# LTM8051.net
KiCad netlist of a schematic drawn in Altium Designer
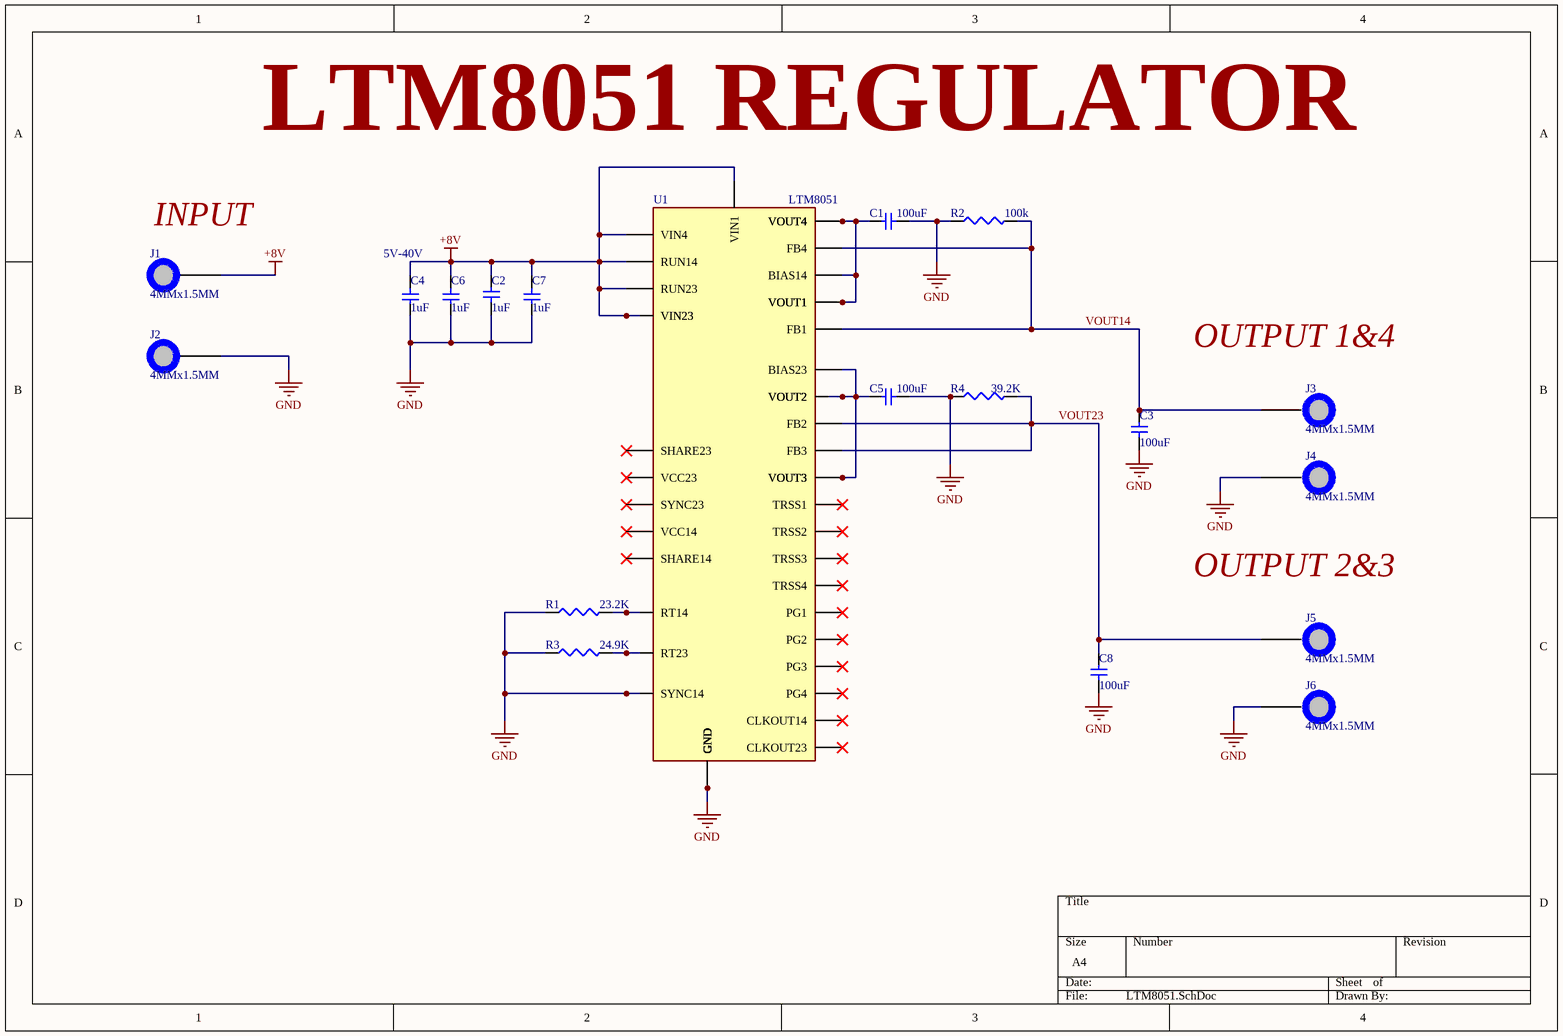
[diagram p0: LTM8051.SchDoc]

(export (version "E")
  (design (tool "Eeschema 10.0.6"))
  (components
    (comp (ref "C1")
      (value "100uF")
      (footprint "C0805")
      (description "100UF 6.3V 20% 0805")
      (fields
        (field (name "MANUFACTURER") "Kyocera AVX")
        (field (name "MANUFACTURER PART NUMBER") "CM21X5R107M06AT")
      )
      (libsource (lib "LTM8051") (part "CM21X5R107M06AT"))
    )
    (comp (ref "C2")
      (value "1uF")
      (footprint "C0805")
      (description "Cap Ceramic 1uF 50V X5R 20% SMD 0805 85°C Punched Paper T/R")
      (fields
        (field (name "MANUFACTURER") "TDK")
        (field (name "MANUFACTURER PART NUMBER") "C2012X5R1H105M085AB")
      )
      (libsource (lib "LTM8051") (part "C2012X5R1H105M085AB"))
    )
    (comp (ref "C3")
      (value "100uF")
      (footprint "C0805")
      (description "100UF 6.3V 20% 0805")
      (fields
        (field (name "MANUFACTURER") "Kyocera AVX")
        (field (name "MANUFACTURER PART NUMBER") "CM21X5R107M06AT")
      )
      (libsource (lib "LTM8051") (part "CM21X5R107M06AT"))
    )
    (comp (ref "C4")
      (value "1uF")
      (footprint "C0805")
      (description "Cap Ceramic 1uF 50V X5R 20% SMD 0805 85°C Punched Paper T/R")
      (fields
        (field (name "MANUFACTURER") "TDK")
        (field (name "MANUFACTURER PART NUMBER") "C2012X5R1H105M085AB")
      )
      (libsource (lib "LTM8051") (part "C2012X5R1H105M085AB"))
    )
    (comp (ref "C5")
      (value "100uF")
      (footprint "C0805")
      (description "100UF 6.3V 20% 0805")
      (fields
        (field (name "MANUFACTURER") "Kyocera AVX")
        (field (name "MANUFACTURER PART NUMBER") "CM21X5R107M06AT")
      )
      (libsource (lib "LTM8051") (part "CM21X5R107M06AT"))
    )
    (comp (ref "C6")
      (value "1uF")
      (footprint "C0805")
      (description "Cap Ceramic 1uF 50V X5R 20% SMD 0805 85°C Punched Paper T/R")
      (fields
        (field (name "MANUFACTURER") "TDK")
        (field (name "MANUFACTURER PART NUMBER") "C2012X5R1H105M085AB")
      )
      (libsource (lib "LTM8051") (part "C2012X5R1H105M085AB"))
    )
    (comp (ref "C7")
      (value "1uF")
      (footprint "C0805")
      (description "Cap Ceramic 1uF 50V X5R 20% SMD 0805 85°C Punched Paper T/R")
      (fields
        (field (name "MANUFACTURER") "TDK")
        (field (name "MANUFACTURER PART NUMBER") "C2012X5R1H105M085AB")
      )
      (libsource (lib "LTM8051") (part "C2012X5R1H105M085AB"))
    )
    (comp (ref "C8")
      (value "100uF")
      (footprint "C0805")
      (description "100UF 6.3V 20% 0805")
      (fields
        (field (name "MANUFACTURER") "Kyocera AVX")
        (field (name "MANUFACTURER PART NUMBER") "CM21X5R107M06AT")
      )
      (libsource (lib "LTM8051") (part "CM21X5R107M06AT"))
    )
    (comp (ref "J1")
      (value "4MMx1.5MM")
      (footprint "PAD_WITH_HOLE_4MMx1MM5")
      (description "Pad with a hole 4mmx1.5mm")
      (libsource (lib "LTM8051") (part "PAD_WITH_HOLE_4MMx1MM5"))
    )
    (comp (ref "J2")
      (value "4MMx1.5MM")
      (footprint "PAD_WITH_HOLE_4MMx1MM5")
      (description "Pad with a hole 4mmx1.5mm")
      (libsource (lib "LTM8051") (part "PAD_WITH_HOLE_4MMx1MM5"))
    )
    (comp (ref "J3")
      (value "4MMx1.5MM")
      (footprint "PAD_WITH_HOLE_4MMx1MM5")
      (description "Pad with a hole 4mmx1.5mm")
      (libsource (lib "LTM8051") (part "PAD_WITH_HOLE_4MMx1MM5"))
    )
    (comp (ref "J4")
      (value "4MMx1.5MM")
      (footprint "PAD_WITH_HOLE_4MMx1MM5")
      (description "Pad with a hole 4mmx1.5mm")
      (libsource (lib "LTM8051") (part "PAD_WITH_HOLE_4MMx1MM5"))
    )
    (comp (ref "J5")
      (value "4MMx1.5MM")
      (footprint "PAD_WITH_HOLE_4MMx1MM5")
      (description "Pad with a hole 4mmx1.5mm")
      (libsource (lib "LTM8051") (part "PAD_WITH_HOLE_4MMx1MM5"))
    )
    (comp (ref "J6")
      (value "4MMx1.5MM")
      (footprint "PAD_WITH_HOLE_4MMx1MM5")
      (description "Pad with a hole 4mmx1.5mm")
      (libsource (lib "LTM8051") (part "PAD_WITH_HOLE_4MMx1MM5"))
    )
    (comp (ref "R1")
      (value "23.2K")
      (footprint "R0805")
      (description "Res Thick Film 0805 23.2K Ohm 1% 1/8W ¦100ppm/¦C SMD Punched Carrier T/R")
      (fields
        (field (name "MANUFACTURER") "Panasonic")
        (field (name "MANUFACTURER PART NUMBER") "ERJ-6ENF2322V")
      )
      (libsource (lib "LTM8051") (part "ERJ-6ENF2322V"))
    )
    (comp (ref "R2")
      (value "100k")
      (footprint "R0805")
      (description "Res Thin Film 0805 100K Ohm 0.1% 1/8W ±25ppm/°C Molded SMD SMD Punched Carrier T/R")
      (fields
        (field (name "MANUFACTURER") "Panasonic")
        (field (name "MANUFACTURER PART NUMBER") "ERA-6AEB104V")
      )
      (libsource (lib "LTM8051") (part "ERA-6AEB104V"))
    )
    (comp (ref "R3")
      (value "24.9K")
      (footprint "R0805")
      (description "SMD Chip Resistor, 24.9 kOhm, ± 1%, 125 mW, 0805 [2012 Metric], Thick Film, General Purpose")
      (fields
        (field (name "MANUFACTURER") "Yageo")
        (field (name "MANUFACTURER PART NUMBER") "AC0805FR-0724K9L")
      )
      (libsource (lib "LTM8051") (part "AC0805FR-0724K9L"))
    )
    (comp (ref "R4")
      (value "39.2K")
      (footprint "R0805")
      (description "Res Thick Film 0805 39.2K Ohm 1% 1/8W ±100ppm/°C Molded SMD Punched Carrier T/R")
      (fields
        (field (name "MANUFACTURER") "Panasonic")
        (field (name "MANUFACTURER PART NUMBER") "ERJ-6ENF3922V")
      )
      (libsource (lib "LTM8051") (part "ERJ-6ENF3922V"))
    )
    (comp (ref "U1")
      (value "LTM8051")
      (footprint "BGA91C80P7X13_625X1125X241")
      (description "Switching Regulator, Current-mode, 2.5A, 3000kHz Switching Freq-Max, Hybrid, PBGA91")
      (fields
        (field (name "MANUFACTURER") "Analog Devices")
        (field (name "MANUFACTURER PART NUMBER") "LTM8051EY#PBF")
      )
      (libsource (lib "LTM8051") (part "LTM8051EY#PBF"))
    )
  )
  (nets
    (net (code "1") (name "+8V") (class "Default")
      (node (ref "C2") (pin "2") (pinfunction "2_2") (pintype "passive"))
      (node (ref "C4") (pin "1") (pinfunction "1_1") (pintype "passive"))
      (node (ref "C6") (pin "1") (pinfunction "1_1") (pintype "passive"))
      (node (ref "C7") (pin "1") (pinfunction "1_1") (pintype "passive"))
      (node (ref "J1") (pin "1") (pinfunction "1_1") (pintype "passive"))
      (node (ref "U1") (pin "C7") (pinfunction "RUN23_C7") (pintype "passive"))
      (node (ref "U1") (pin "D7") (pinfunction "RUN14_D7") (pintype "passive"))
      (node (ref "U1") (pin "E7") (pinfunction "VIN1_E7") (pintype "passive"))
      (node (ref "U1") (pin "F7") (pinfunction "VIN4_F7") (pintype "passive"))
      (node (ref "U1") (pin "G1") (pinfunction "VIN23_G1") (pintype "passive"))
      (node (ref "U1") (pin "H1") (pinfunction "VIN23_H1") (pintype "passive"))
    )
    (net (code "2") (name "/VOUT14") (class "Default")
      (node (ref "C3") (pin "2") (pinfunction "2_2") (pintype "passive"))
      (node (ref "J3") (pin "1") (pinfunction "1_1") (pintype "passive"))
      (node (ref "R2") (pin "2") (pinfunction "2_2") (pintype "passive"))
      (node (ref "U1") (pin "L1") (pinfunction "FB4_L1") (pintype "passive"))
      (node (ref "U1") (pin "L2") (pinfunction "FB1_L2") (pintype "passive"))
    )
    (net (code "3") (name "/VOUT23") (class "Default")
      (node (ref "C8") (pin "2") (pinfunction "2_2") (pintype "passive"))
      (node (ref "J5") (pin "1") (pinfunction "1_1") (pintype "passive"))
      (node (ref "R4") (pin "2") (pinfunction "2_2") (pintype "passive"))
      (node (ref "U1") (pin "D1") (pinfunction "FB3_D1") (pintype "passive"))
      (node (ref "U1") (pin "D2") (pinfunction "FB2_D2") (pintype "passive"))
    )
    (net (code "4") (name "GND") (class "Default")
      (node (ref "C1") (pin "1") (pinfunction "1_1") (pintype "passive"))
      (node (ref "C2") (pin "1") (pinfunction "1_1") (pintype "passive"))
      (node (ref "C3") (pin "1") (pinfunction "1_1") (pintype "passive"))
      (node (ref "C4") (pin "2") (pinfunction "2_2") (pintype "passive"))
      (node (ref "C5") (pin "1") (pinfunction "1_1") (pintype "passive"))
      (node (ref "C6") (pin "2") (pinfunction "2_2") (pintype "passive"))
      (node (ref "C7") (pin "2") (pinfunction "2_2") (pintype "passive"))
      (node (ref "C8") (pin "1") (pinfunction "1_1") (pintype "passive"))
      (node (ref "J2") (pin "1") (pinfunction "1_1") (pintype "passive"))
      (node (ref "J4") (pin "1") (pinfunction "1_1") (pintype "passive"))
      (node (ref "J6") (pin "1") (pinfunction "1_1") (pintype "passive"))
      (node (ref "R1") (pin "1") (pinfunction "1_1") (pintype "passive"))
      (node (ref "R2") (pin "1") (pinfunction "1_1") (pintype "passive"))
      (node (ref "R3") (pin "1") (pinfunction "1_1") (pintype "passive"))
      (node (ref "R4") (pin "1") (pinfunction "1_1") (pintype "passive"))
      (node (ref "U1") (pin "B3") (pinfunction "GND_B3") (pintype "passive"))
      (node (ref "U1") (pin "B4") (pinfunction "GND_B4") (pintype "passive"))
      (node (ref "U1") (pin "B5") (pinfunction "GND_B5") (pintype "passive"))
      (node (ref "U1") (pin "C3") (pinfunction "GND_C3") (pintype "passive"))
      (node (ref "U1") (pin "C4") (pinfunction "GND_C4") (pintype "passive"))
      (node (ref "U1") (pin "C5") (pinfunction "GND_C5") (pintype "passive"))
      (node (ref "U1") (pin "D3") (pinfunction "GND_D3") (pintype "passive"))
      (node (ref "U1") (pin "D4") (pinfunction "GND_D4") (pintype "passive"))
      (node (ref "U1") (pin "D5") (pinfunction "GND_D5") (pintype "passive"))
      (node (ref "U1") (pin "E1") (pinfunction "GND_E1") (pintype "passive"))
      (node (ref "U1") (pin "E2") (pinfunction "GND_E2") (pintype "passive"))
      (node (ref "U1") (pin "E3") (pinfunction "GND_E3") (pintype "passive"))
      (node (ref "U1") (pin "E4") (pinfunction "GND_E4") (pintype "passive"))
      (node (ref "U1") (pin "E5") (pinfunction "GND_E5") (pintype "passive"))
      (node (ref "U1") (pin "F1") (pinfunction "GND_F1") (pintype "passive"))
      (node (ref "U1") (pin "F2") (pinfunction "GND_F2") (pintype "passive"))
      (node (ref "U1") (pin "F3") (pinfunction "GND_F3") (pintype "passive"))
      (node (ref "U1") (pin "F4") (pinfunction "GND_F4") (pintype "passive"))
      (node (ref "U1") (pin "F5") (pinfunction "GND_F5") (pintype "passive"))
      (node (ref "U1") (pin "F6") (pinfunction "SYNC14_F6") (pintype "passive"))
      (node (ref "U1") (pin "G2") (pinfunction "GND_G2") (pintype "passive"))
      (node (ref "U1") (pin "G3") (pinfunction "GND_21_G3") (pintype "passive"))
      (node (ref "U1") (pin "G4") (pinfunction "GND_G4") (pintype "passive"))
      (node (ref "U1") (pin "G5") (pinfunction "GND_G5") (pintype "passive"))
      (node (ref "U1") (pin "G6") (pinfunction "GND_G6") (pintype "passive"))
      (node (ref "U1") (pin "G7") (pinfunction "GND_G7") (pintype "passive"))
      (node (ref "U1") (pin "H2") (pinfunction "GND_H2") (pintype "passive"))
      (node (ref "U1") (pin "H3") (pinfunction "GND_H3") (pintype "passive"))
      (node (ref "U1") (pin "H4") (pinfunction "GND_H4") (pintype "passive"))
      (node (ref "U1") (pin "H5") (pinfunction "GND_H5") (pintype "passive"))
      (node (ref "U1") (pin "H6") (pinfunction "GND_H6") (pintype "passive"))
      (node (ref "U1") (pin "H7") (pinfunction "GND_H7") (pintype "passive"))
      (node (ref "U1") (pin "J3") (pinfunction "GND_J3") (pintype "passive"))
      (node (ref "U1") (pin "J4") (pinfunction "GND_J4") (pintype "passive"))
      (node (ref "U1") (pin "J5") (pinfunction "GND_J5") (pintype "passive"))
      (node (ref "U1") (pin "J6") (pinfunction "GND_J6") (pintype "passive"))
      (node (ref "U1") (pin "J7") (pinfunction "GND_J7") (pintype "passive"))
      (node (ref "U1") (pin "K3") (pinfunction "GND_K3") (pintype "passive"))
      (node (ref "U1") (pin "K4") (pinfunction "GND_K4") (pintype "passive"))
      (node (ref "U1") (pin "K5") (pinfunction "GND_K5") (pintype "passive"))
      (node (ref "U1") (pin "L3") (pinfunction "GND_L3") (pintype "passive"))
      (node (ref "U1") (pin "L4") (pinfunction "GND_L4") (pintype "passive"))
      (node (ref "U1") (pin "L5") (pinfunction "GND_L5") (pintype "passive"))
      (node (ref "U1") (pin "M3") (pinfunction "GND_M3") (pintype "passive"))
      (node (ref "U1") (pin "M4") (pinfunction "GND_M4") (pintype "passive"))
      (node (ref "U1") (pin "M5") (pinfunction "GND_M5") (pintype "passive"))
    )
    (net (code "5") (name "Net-(U1-BIAS14)") (class "Default")
      (node (ref "C1") (pin "2") (pinfunction "2_2") (pintype "passive"))
      (node (ref "U1") (pin "M1") (pinfunction "VOUT1_M1") (pintype "passive"))
      (node (ref "U1") (pin "M2") (pinfunction "VOUT1_M2") (pintype "passive"))
      (node (ref "U1") (pin "M6") (pinfunction "VOUT4_M6") (pintype "passive"))
      (node (ref "U1") (pin "M7") (pinfunction "VOUT4_M7") (pintype "passive"))
      (node (ref "U1") (pin "N1") (pinfunction "VOUT1_N1") (pintype "passive"))
      (node (ref "U1") (pin "N2") (pinfunction "VOUT1_N2") (pintype "passive"))
      (node (ref "U1") (pin "N3") (pinfunction "BIAS14_N3") (pintype "passive"))
      (node (ref "U1") (pin "N6") (pinfunction "VOUT4_N6") (pintype "passive"))
      (node (ref "U1") (pin "N7") (pinfunction "VOUT4_N7") (pintype "passive"))
    )
    (net (code "6") (name "Net-(U1-BIAS23)") (class "Default")
      (node (ref "C5") (pin "2") (pinfunction "2_2") (pintype "passive"))
      (node (ref "U1") (pin "A1") (pinfunction "VOUT3_A1") (pintype "passive"))
      (node (ref "U1") (pin "A2") (pinfunction "VOUT3_A2") (pintype "passive"))
      (node (ref "U1") (pin "A5") (pinfunction "BIAS23_A5") (pintype "passive"))
      (node (ref "U1") (pin "A6") (pinfunction "VOUT2_A6") (pintype "passive"))
      (node (ref "U1") (pin "A7") (pinfunction "VOUT2_A7") (pintype "passive"))
      (node (ref "U1") (pin "B1") (pinfunction "VOUT3_B1") (pintype "passive"))
      (node (ref "U1") (pin "B2") (pinfunction "VOUT3_B2") (pintype "passive"))
      (node (ref "U1") (pin "B6") (pinfunction "VOUT2_B6") (pintype "passive"))
      (node (ref "U1") (pin "B7") (pinfunction "VOUT2_B7") (pintype "passive"))
    )
    (net (code "7") (name "Net-(U1-RT14)") (class "Default")
      (node (ref "R1") (pin "2") (pinfunction "2_2") (pintype "passive"))
      (node (ref "U1") (pin "K1") (pinfunction "RT14_K1") (pintype "passive"))
    )
    (net (code "8") (name "Net-(U1-RT23)") (class "Default")
      (node (ref "R3") (pin "2") (pinfunction "2_2") (pintype "passive"))
      (node (ref "U1") (pin "J1") (pinfunction "RT23_J1") (pintype "passive"))
    )
    (net (code "9") (name "unconnected-(U1-CLKOUT14-PadD6)") (class "Default")
      (node (ref "U1") (pin "D6") (pinfunction "CLKOUT14_D6") (pintype "passive+no_connect"))
    )
    (net (code "10") (name "unconnected-(U1-CLKOUT23-PadC6)") (class "Default")
      (node (ref "U1") (pin "C6") (pinfunction "CLKOUT23_C6") (pintype "passive+no_connect"))
    )
    (net (code "11") (name "unconnected-(U1-PG1-PadL6)") (class "Default")
      (node (ref "U1") (pin "L6") (pinfunction "PG1_L6") (pintype "passive+no_connect"))
    )
    (net (code "12") (name "unconnected-(U1-PG2-PadK6)") (class "Default")
      (node (ref "U1") (pin "K6") (pinfunction "PG2_K6") (pintype "passive+no_connect"))
    )
    (net (code "13") (name "unconnected-(U1-PG3-PadK7)") (class "Default")
      (node (ref "U1") (pin "K7") (pinfunction "PG3_K7") (pintype "passive+no_connect"))
    )
    (net (code "14") (name "unconnected-(U1-PG4-PadL7)") (class "Default")
      (node (ref "U1") (pin "L7") (pinfunction "PG4_L7") (pintype "passive+no_connect"))
    )
    (net (code "15") (name "unconnected-(U1-SHARE14-PadN5)") (class "Default")
      (node (ref "U1") (pin "N5") (pinfunction "SHARE14_N5") (pintype "passive+no_connect"))
    )
    (net (code "16") (name "unconnected-(U1-SHARE23-PadA3)") (class "Default")
      (node (ref "U1") (pin "A3") (pinfunction "SHARE23_A3") (pintype "passive+no_connect"))
    )
    (net (code "17") (name "unconnected-(U1-SYNC23-PadE6)") (class "Default")
      (node (ref "U1") (pin "E6") (pinfunction "SYNC23_E6") (pintype "passive+no_connect"))
    )
    (net (code "18") (name "unconnected-(U1-TRSS1-PadJ2)") (class "Default")
      (node (ref "U1") (pin "J2") (pinfunction "TRSS1_J2") (pintype "passive+no_connect"))
    )
    (net (code "19") (name "unconnected-(U1-TRSS2-PadC2)") (class "Default")
      (node (ref "U1") (pin "C2") (pinfunction "TRSS2_C2") (pintype "passive+no_connect"))
    )
    (net (code "20") (name "unconnected-(U1-TRSS3-PadC1)") (class "Default")
      (node (ref "U1") (pin "C1") (pinfunction "TRSS3_C1") (pintype "passive+no_connect"))
    )
    (net (code "21") (name "unconnected-(U1-TRSS4-PadK2)") (class "Default")
      (node (ref "U1") (pin "K2") (pinfunction "TRSS4_K2") (pintype "passive+no_connect"))
    )
    (net (code "22") (name "unconnected-(U1-VCC14-PadN4)") (class "Default")
      (node (ref "U1") (pin "N4") (pinfunction "VCC14_N4") (pintype "passive+no_connect"))
    )
    (net (code "23") (name "unconnected-(U1-VCC23-PadA4)") (class "Default")
      (node (ref "U1") (pin "A4") (pinfunction "VCC23_A4") (pintype "passive+no_connect"))
    )
  )
)
